# Controller.net
KiCad netlist of a schematic drawn in Altium Designer
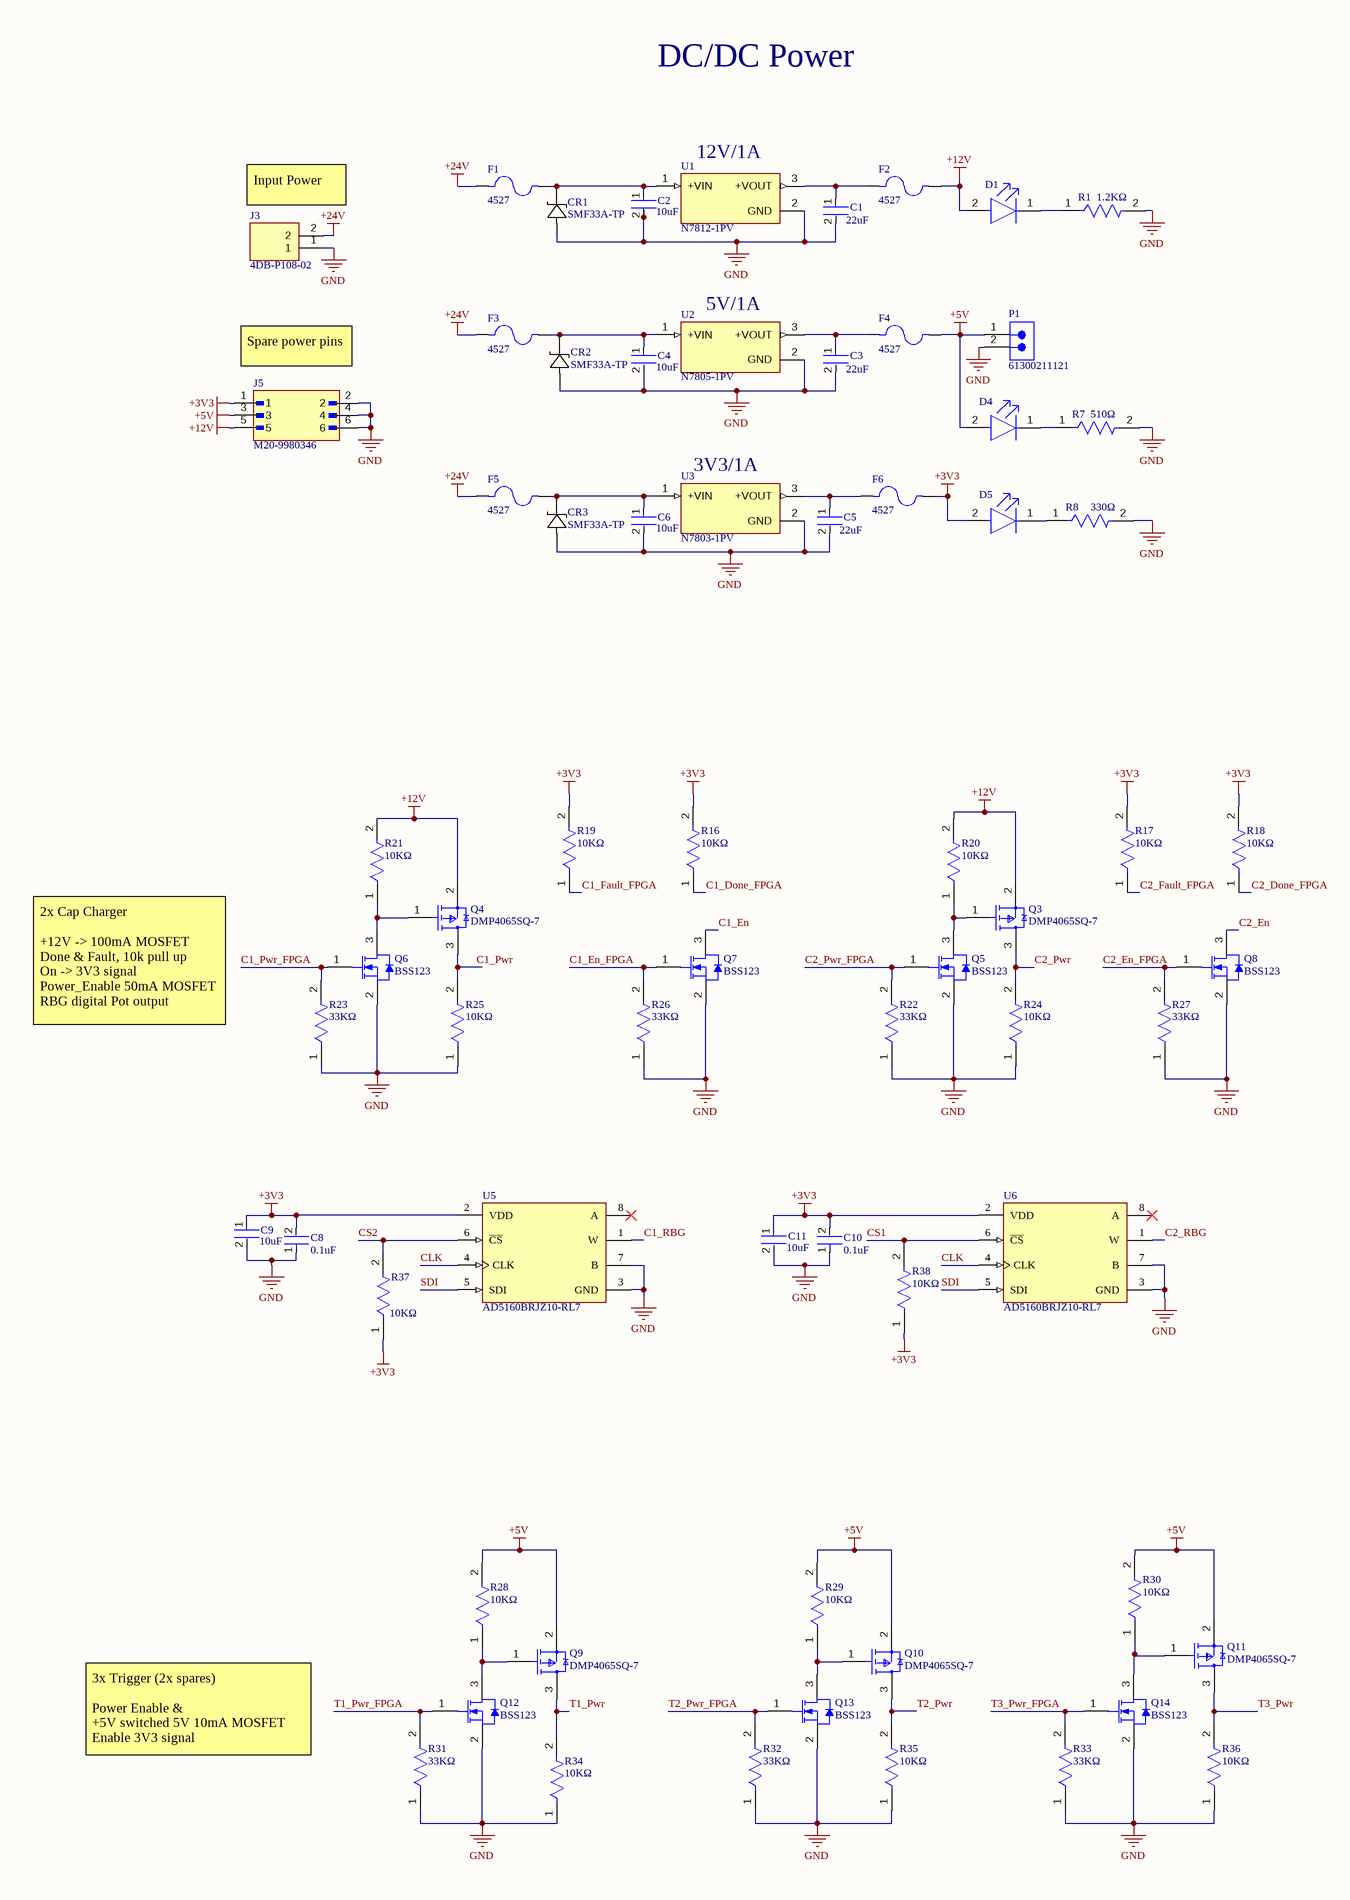
[diagram p0: Controller.SchDoc, left]
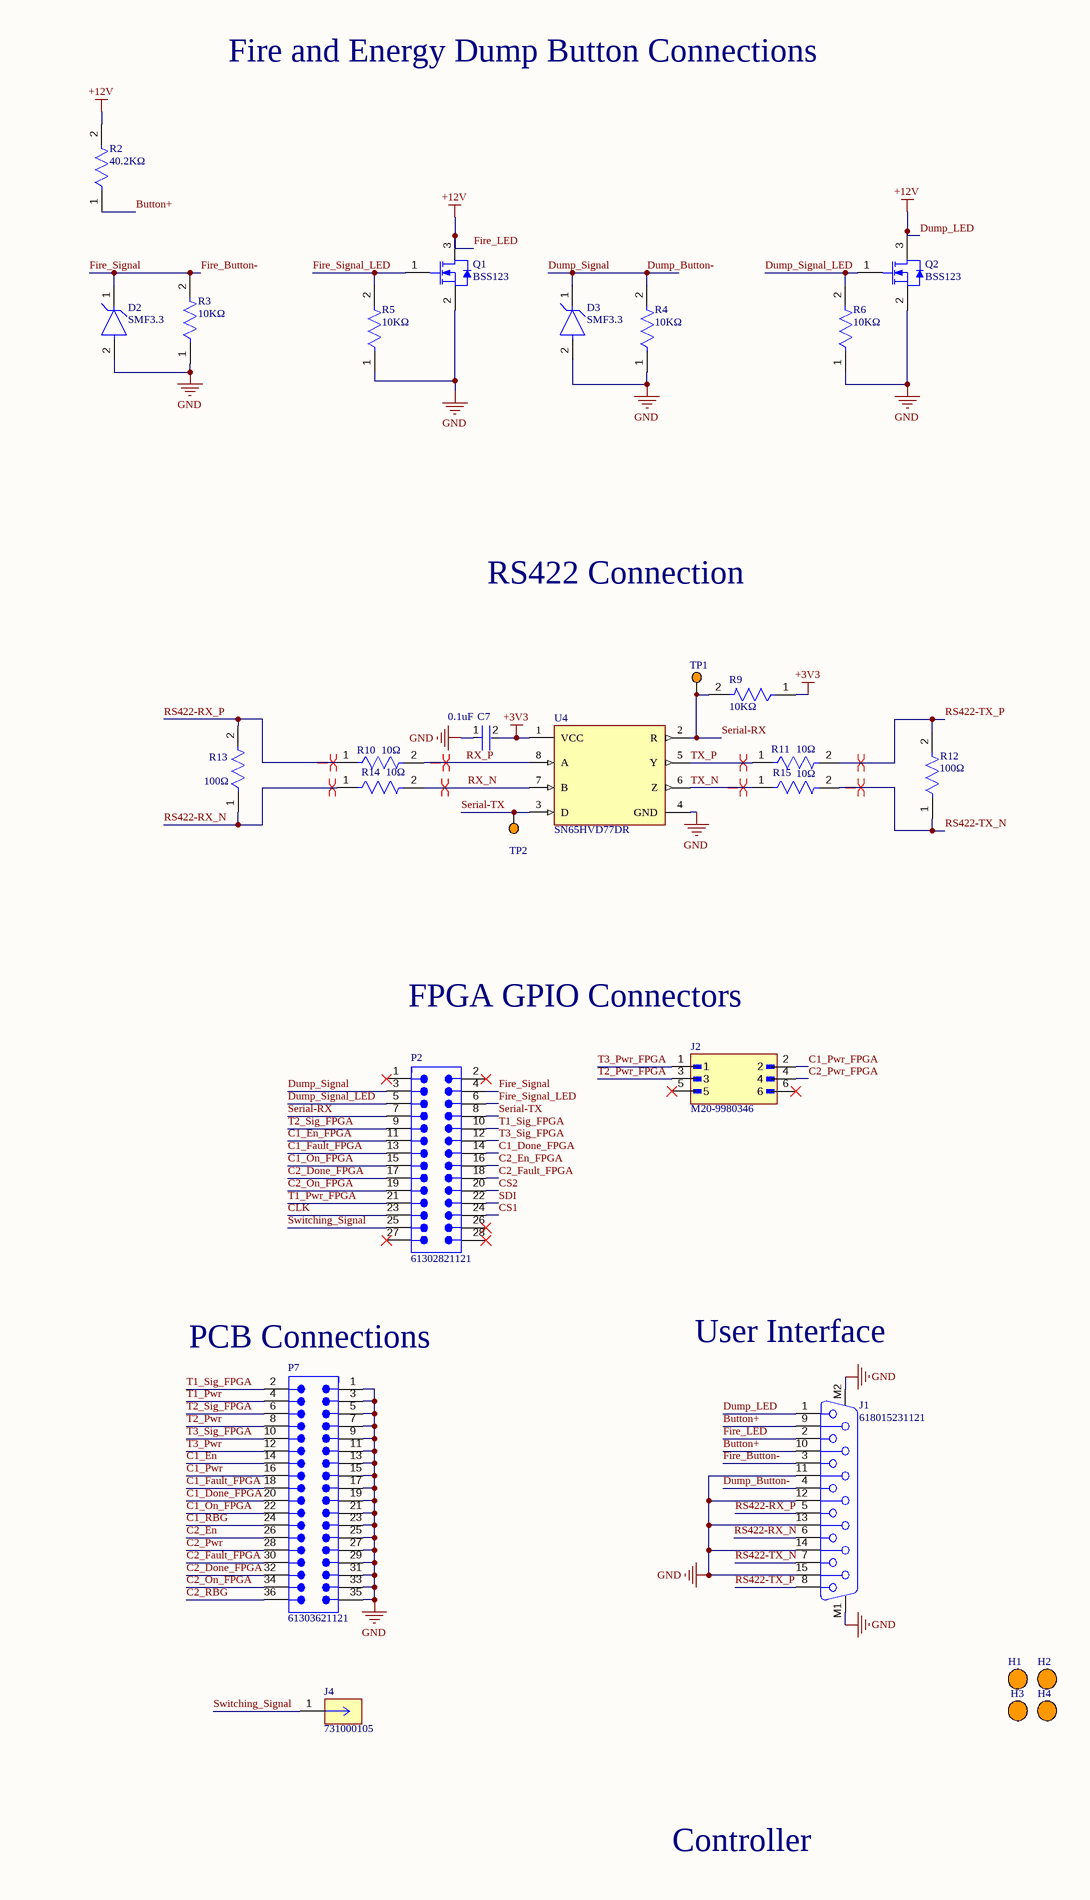
[diagram p1: Controller.SchDoc, right]

(export (version "E")
  (design (tool "Eeschema 10.0.6"))
  (components
    (comp (ref "C1")
      (value "CC0805MKX5R8BB226")
      (footprint "FP-CC0805-0_2-1_45-IPC_C")
      (description "CAP CER 22UF 25V X5R 0805")
      (fields (field (name "CAPACITANCE") "22uF") (field (name "TOLERANCE") "20%"))
      (libsource (lib "Altium Content Vault") (part "11868f565c42a9108669ba33697ecf6"))
    )
    (comp (ref "C2")
      (value "CL32B106KBJNNNE")
      (footprint "FP-CL32-IPC_C")
      (description "Cap Ceramic 10uF 50V X7R ±10% SMD 1210 +125°C Embossed T/R")
      (fields
        (field (name "CAPACITANCE") "10uF")
        (field (name "TOLERANCE") "10%")
        (field (name "VOLTAGE") "50V")
      )
      (libsource (lib "Altium Content Vault") (part "b4654b650e69147ec39a6b967a45e02"))
    )
    (comp (ref "C3")
      (value "CC0805MKX5R8BB226")
      (footprint "FP-CC0805-0_2-1_45-IPC_C")
      (description "CAP CER 22UF 25V X5R 0805")
      (fields (field (name "CAPACITANCE") "22uF") (field (name "TOLERANCE") "20%"))
      (libsource (lib "Altium Content Vault") (part "11868f565c42a9108669ba33697ecf6"))
    )
    (comp (ref "C4")
      (value "CL32B106KBJNNNE")
      (footprint "FP-CL32-IPC_C")
      (description "Cap Ceramic 10uF 50V X7R ±10% SMD 1210 +125°C Embossed T/R")
      (fields
        (field (name "CAPACITANCE") "10uF")
        (field (name "TOLERANCE") "10%")
        (field (name "VOLTAGE") "50V")
      )
      (libsource (lib "Altium Content Vault") (part "b4654b650e69147ec39a6b967a45e02"))
    )
    (comp (ref "C5")
      (value "CC0805MKX5R8BB226")
      (footprint "FP-CC0805-0_2-1_45-IPC_C")
      (description "CAP CER 22UF 25V X5R 0805")
      (fields (field (name "CAPACITANCE") "22uF") (field (name "TOLERANCE") "20%"))
      (libsource (lib "Altium Content Vault") (part "11868f565c42a9108669ba33697ecf6"))
    )
    (comp (ref "C6")
      (value "CL32B106KBJNNNE")
      (footprint "FP-CL32-IPC_C")
      (description "Cap Ceramic 10uF 50V X7R ±10% SMD 1210 +125°C Embossed T/R")
      (fields
        (field (name "CAPACITANCE") "10uF")
        (field (name "TOLERANCE") "10%")
        (field (name "VOLTAGE") "50V")
      )
      (libsource (lib "Altium Content Vault") (part "b4654b650e69147ec39a6b967a45e02"))
    )
    (comp (ref "C7")
      (value "0.1uF")
      (footprint "FP-CC0603-DA-IPC_A")
      (description "CC0603JRX7R9BB104\r\nCAP CER 0.1UF 50V X7R 0603")
      (fields (field (name "TOLERANCE") "5%") (field (name "MANUFACTURER") "Yageo"))
      (libsource (lib "Altium Content Vault") (part "02cd4be3c70576c341d710602a673aa"))
    )
    (comp (ref "C8")
      (value "0.1uF")
      (footprint "FP-CC0603-DA-IPC_A")
      (description "CC0603JRX7R9BB104\r\nCAP CER 0.1UF 50V X7R 0603")
      (fields (field (name "TOLERANCE") "5%") (field (name "MANUFACTURER") "Yageo"))
      (libsource (lib "Altium Content Vault") (part "02cd4be3c70576c341d710602a673aa"))
    )
    (comp (ref "C9")
      (value "CL32B106KBJNNNE")
      (footprint "FP-CL32-IPC_C")
      (description "Cap Ceramic 10uF 50V X7R ±10% SMD 1210 +125°C Embossed T/R")
      (fields
        (field (name "CAPACITANCE") "10uF")
        (field (name "TOLERANCE") "10%")
        (field (name "VOLTAGE") "50V")
      )
      (libsource (lib "Altium Content Vault") (part "b4654b650e69147ec39a6b967a45e02"))
    )
    (comp (ref "C10")
      (value "0.1uF")
      (footprint "FP-CC0603-DA-IPC_A")
      (description "CC0603JRX7R9BB104\r\nCAP CER 0.1UF 50V X7R 0603")
      (fields (field (name "TOLERANCE") "5%") (field (name "MANUFACTURER") "Yageo"))
      (libsource (lib "Altium Content Vault") (part "02cd4be3c70576c341d710602a673aa"))
    )
    (comp (ref "C11")
      (value "CL32B106KBJNNNE")
      (footprint "FP-CL32-IPC_C")
      (description "Cap Ceramic 10uF 50V X7R ±10% SMD 1210 +125°C Embossed T/R")
      (fields
        (field (name "CAPACITANCE") "10uF")
        (field (name "TOLERANCE") "10%")
        (field (name "VOLTAGE") "50V")
      )
      (libsource (lib "Altium Content Vault") (part "b4654b650e69147ec39a6b967a45e02"))
    )
    (comp (ref "CR1")
      (value "SMF33A-TP")
      (footprint "SOD-123FL_MCC")
      (description "No Description Available")
      (fields (field (name "COPYRIGHT") "Copyright (C) 2025 Ultra Librarian. All rights reserved."))
      (libsource (lib "Schlib1") (part "SMF33A-TP"))
    )
    (comp (ref "CR2")
      (value "SMF33A-TP")
      (footprint "SOD-123FL_MCC")
      (description "No Description Available")
      (fields (field (name "COPYRIGHT") "Copyright (C) 2025 Ultra Librarian. All rights reserved."))
      (libsource (lib "Schlib1") (part "SMF33A-TP"))
    )
    (comp (ref "CR3")
      (value "SMF33A-TP")
      (footprint "SOD-123FL_MCC")
      (description "No Description Available")
      (fields (field (name "COPYRIGHT") "Copyright (C) 2025 Ultra Librarian. All rights reserved."))
      (libsource (lib "Schlib1") (part "SMF33A-TP"))
    )
    (comp (ref "D1")
      (value "LTST-C190GKT")
      (footprint "FP-LTST-C190GKT-MFG")
      (description "LED GREEN CLEAR CHIP SMD")
      (fields (field (name "VOLTAGE") "2V"))
      (libsource (lib "Altium Content Vault") (part "8706943c75ba83719d021d2fdc84c58"))
    )
    (comp (ref "D2")
      (value "SMF3.3")
      (footprint "FP-SMF3_3-MFG")
      (description "TVS DIODE 3.3V 6.8V SOD123FL")
      (fields
        (field (name "MANUFACTURER") "Littelfuse")
        (field (name "OCTOPART") "https://octopart.com/smf3.3-littelfuse-75449841")
      )
      (libsource (lib "Altium Content Vault") (part "f813f71cba58e380607f5dd3caf9714"))
    )
    (comp (ref "D3")
      (value "SMF3.3")
      (footprint "FP-SMF3_3-MFG")
      (description "TVS DIODE 3.3V 6.8V SOD123FL")
      (fields
        (field (name "MANUFACTURER") "Littelfuse")
        (field (name "OCTOPART") "https://octopart.com/smf3.3-littelfuse-75449841")
      )
      (libsource (lib "Altium Content Vault") (part "f813f71cba58e380607f5dd3caf9714"))
    )
    (comp (ref "D4")
      (value "LTST-C190GKT")
      (footprint "FP-LTST-C190GKT-MFG")
      (description "LED GREEN CLEAR CHIP SMD")
      (fields (field (name "VOLTAGE") "2V"))
      (libsource (lib "Altium Content Vault") (part "8706943c75ba83719d021d2fdc84c58"))
    )
    (comp (ref "D5")
      (value "LTST-C190GKT")
      (footprint "FP-LTST-C190GKT-MFG")
      (description "LED GREEN CLEAR CHIP SMD")
      (fields (field (name "VOLTAGE") "2V"))
      (libsource (lib "Altium Content Vault") (part "8706943c75ba83719d021d2fdc84c58"))
    )
    (comp (ref "F1")
      (value "4527")
      (footprint "FUSE_4527")
      (description "5mm Low Profile Holder")
      (fields (field (name "MF") "Keystone"))
      (libsource (lib "Schlib1") (part "4527"))
    )
    (comp (ref "F2")
      (value "4527")
      (footprint "FUSE_4527")
      (description "5mm Low Profile Holder")
      (fields (field (name "MF") "Keystone"))
      (libsource (lib "Schlib1") (part "4527"))
    )
    (comp (ref "F3")
      (value "4527")
      (footprint "FUSE_4527")
      (description "5mm Low Profile Holder")
      (fields (field (name "MF") "Keystone"))
      (libsource (lib "Schlib1") (part "4527"))
    )
    (comp (ref "F4")
      (value "4527")
      (footprint "FUSE_4527")
      (description "5mm Low Profile Holder")
      (fields (field (name "MF") "Keystone"))
      (libsource (lib "Schlib1") (part "4527"))
    )
    (comp (ref "F5")
      (value "4527")
      (footprint "FUSE_4527")
      (description "5mm Low Profile Holder")
      (fields (field (name "MF") "Keystone"))
      (libsource (lib "Schlib1") (part "4527"))
    )
    (comp (ref "F6")
      (value "4527")
      (footprint "FUSE_4527")
      (description "5mm Low Profile Holder")
      (fields (field (name "MF") "Keystone"))
      (libsource (lib "Schlib1") (part "4527"))
    )
    (comp (ref "H1") (value "M3_Hole") (footprint "M3_Hole") (libsource (lib "Schlib1") (part "M3_Hole")))
    (comp (ref "H2") (value "M3_Hole") (footprint "M3_Hole") (libsource (lib "Schlib1") (part "M3_Hole")))
    (comp (ref "H3") (value "M3_Hole") (footprint "M3_Hole") (libsource (lib "Schlib1") (part "M3_Hole")))
    (comp (ref "H4") (value "M3_Hole") (footprint "M3_Hole") (libsource (lib "Schlib1") (part "M3_Hole")))
    (comp (ref "J1")
      (value "618015231121")
      (footprint "618015231121")
      (libsource (lib "Altium Content Vault") (part "D-Sub_Female_15p"))
    )
    (comp (ref "J2")
      (value "M20-9980346")
      (footprint "HARWIN_M20-9980346")
      (libsource (lib "Schlib1") (part "M20-9980346"))
    )
    (comp (ref "J3")
      (value "4DB-P108-02")
      (footprint "TE_2-1437667-4")
      (description "Conn; Term Strip; Barrier; 2Pole; 8.26mmPitch; SnglRow; 22-12; Series 4DB; 20A; 150V")
      (fields (field (name "MF") "TE Connectivity"))
      (libsource (lib "Schlib1") (part "4DB-P108-02"))
    )
    (comp (ref "J4")
      (value "731000105")
      (footprint "CONN_73100-0105_MOL")
      (description "BNC JACK, RA, RECEPTACLE, 50 OHM ¦ Molex Incorporated 73100-0105")
      (fields (field (name "MF") "Molex") (field (name "MP") "73100-0105"))
      (libsource (lib "Schlib1") (part "731000105"))
    )
    (comp (ref "J5")
      (value "M20-9980346")
      (footprint "HARWIN_M20-9980346")
      (libsource (lib "Schlib1") (part "M20-9980346"))
    )
    (comp (ref "P1")
      (value "61300211121")
      (footprint "61300211121")
      (libsource (lib "Altium Content Vault") (part "Header_Male_1R_02P"))
    )
    (comp (ref "P2")
      (value "61302821121")
      (footprint "61302821121")
      (libsource (lib "Altium Content Vault") (part "Header_Male_2R_28P"))
    )
    (comp (ref "P7")
      (value "61303621121")
      (footprint "61303621121")
      (libsource (lib "Altium Content Vault") (part "Header_Male_2R_36P"))
    )
    (comp (ref "Q1")
      (value "BSS123")
      (footprint "FAIR-SOT23-3_V")
      (fields (field (name "MANUFACTURER") "Fairchild"))
      (libsource (lib "Altium Content Vault") (part "NEMOS-GSD-3"))
    )
    (comp (ref "Q2")
      (value "BSS123")
      (footprint "FAIR-SOT23-3_V")
      (fields (field (name "MANUFACTURER") "Fairchild"))
      (libsource (lib "Altium Content Vault") (part "NEMOS-GSD-3"))
    )
    (comp (ref "Q3")
      (value "DMP4065SQ-7")
      (footprint "FP-SOT23-IPC_C")
      (description "Mosfet, P-Ch, 40V, 2.4A, 150Deg C, 0.72W")
      (fields (field (name "MANUFACTURER") "Diodes Inc"))
      (libsource (lib "Space Machines Company Pty Ltd") (part "90d26376f95f59a583a7107ec0b7fdb"))
    )
    (comp (ref "Q4")
      (value "DMP4065SQ-7")
      (footprint "FP-SOT23-IPC_C")
      (description "Mosfet, P-Ch, 40V, 2.4A, 150Deg C, 0.72W")
      (fields (field (name "MANUFACTURER") "Diodes Inc"))
      (libsource (lib "Space Machines Company Pty Ltd") (part "90d26376f95f59a583a7107ec0b7fdb"))
    )
    (comp (ref "Q5")
      (value "BSS123")
      (footprint "FAIR-SOT23-3_V")
      (description "Transistor MOSFET Negative Channel 100 Volt 0.17A 3-Pin SOT-23")
      (fields (field (name "MANUFACTURER") "On Semi"))
      (libsource (lib "Space Machines Company Pty Ltd") (part "NEMOS-GSD-3"))
    )
    (comp (ref "Q6")
      (value "BSS123")
      (footprint "FAIR-SOT23-3_V")
      (description "Transistor MOSFET Negative Channel 100 Volt 0.17A 3-Pin SOT-23")
      (fields (field (name "MANUFACTURER") "On Semi"))
      (libsource (lib "Space Machines Company Pty Ltd") (part "NEMOS-GSD-3"))
    )
    (comp (ref "Q7")
      (value "BSS123")
      (footprint "FAIR-SOT23-3_V")
      (description "Transistor MOSFET Negative Channel 100 Volt 0.17A 3-Pin SOT-23")
      (fields (field (name "MANUFACTURER") "On Semi"))
      (libsource (lib "Space Machines Company Pty Ltd") (part "NEMOS-GSD-3"))
    )
    (comp (ref "Q8")
      (value "BSS123")
      (footprint "FAIR-SOT23-3_V")
      (description "Transistor MOSFET Negative Channel 100 Volt 0.17A 3-Pin SOT-23")
      (fields (field (name "MANUFACTURER") "On Semi"))
      (libsource (lib "Space Machines Company Pty Ltd") (part "NEMOS-GSD-3"))
    )
    (comp (ref "Q9")
      (value "DMP4065SQ-7")
      (footprint "FP-SOT23-IPC_C")
      (description "Mosfet, P-Ch, 40V, 2.4A, 150Deg C, 0.72W")
      (fields (field (name "MANUFACTURER") "Diodes Inc"))
      (libsource (lib "Space Machines Company Pty Ltd") (part "90d26376f95f59a583a7107ec0b7fdb"))
    )
    (comp (ref "Q10")
      (value "DMP4065SQ-7")
      (footprint "FP-SOT23-IPC_C")
      (description "Mosfet, P-Ch, 40V, 2.4A, 150Deg C, 0.72W")
      (fields (field (name "MANUFACTURER") "Diodes Inc"))
      (libsource (lib "Space Machines Company Pty Ltd") (part "90d26376f95f59a583a7107ec0b7fdb"))
    )
    (comp (ref "Q11")
      (value "DMP4065SQ-7")
      (footprint "FP-SOT23-IPC_C")
      (description "Mosfet, P-Ch, 40V, 2.4A, 150Deg C, 0.72W")
      (fields (field (name "MANUFACTURER") "Diodes Inc"))
      (libsource (lib "Space Machines Company Pty Ltd") (part "90d26376f95f59a583a7107ec0b7fdb"))
    )
    (comp (ref "Q12")
      (value "BSS123")
      (footprint "FAIR-SOT23-3_V")
      (description "Transistor MOSFET Negative Channel 100 Volt 0.17A 3-Pin SOT-23")
      (fields (field (name "MANUFACTURER") "On Semi"))
      (libsource (lib "Space Machines Company Pty Ltd") (part "NEMOS-GSD-3"))
    )
    (comp (ref "Q13")
      (value "BSS123")
      (footprint "FAIR-SOT23-3_V")
      (description "Transistor MOSFET Negative Channel 100 Volt 0.17A 3-Pin SOT-23")
      (fields (field (name "MANUFACTURER") "On Semi"))
      (libsource (lib "Space Machines Company Pty Ltd") (part "NEMOS-GSD-3"))
    )
    (comp (ref "Q14")
      (value "BSS123")
      (footprint "FAIR-SOT23-3_V")
      (description "Transistor MOSFET Negative Channel 100 Volt 0.17A 3-Pin SOT-23")
      (fields (field (name "MANUFACTURER") "On Semi"))
      (libsource (lib "Space Machines Company Pty Ltd") (part "NEMOS-GSD-3"))
    )
    (comp (ref "R1")
      (value "RT0805FRE071K2L")
      (footprint "FP-RT0805-MFG")
      (description "RES SMD 1.2K OHM 1% 1/8W 0805")
      (fields
        (field (name "TOLERANCE") "0.0001")
        (field (name "RESISTANCE") "1.2KΩ")
        (field (name "OCTOPART") "https://octopart.com/rt0805fre071k2l-yageo-40048706")
      )
      (libsource (lib "Altium Content Vault") (part "1029c3af85768c4190bb7ad29bc67b5"))
    )
    (comp (ref "R2")
      (value "RT0805BRE0740K2L")
      (footprint "FP-RT0805-MFG")
      (description "RES SMD 40.2K OHM 0.1% 1/8W 0805")
      (fields
        (field (name "RESISTANCE") "40.2KΩ")
        (field (name "TOLERANCE") "0.0025")
        (field (name "MANUFACTURER") "Yageo")
      )
      (libsource (lib "Altium Content Vault") (part "1029c3af85768c4190bb7ad29bc67b5"))
    )
    (comp (ref "R3")
      (value "10KΩ")
      (footprint "FP-RT0805-MFG")
      (description "RES 10.0K OHM 1/8W 1% SMD 0805")
      (fields
        (field (name "TOLERANCE") "0.0001")
        (field (name "OCTOPART") "https://octopart.com/rt0805fre0710kl-yageo-40301150")
      )
      (libsource (lib "Altium Content Vault") (part "1029c3af85768c4190bb7ad29bc67b5"))
    )
    (comp (ref "R4")
      (value "10KΩ")
      (footprint "FP-RT0805-MFG")
      (description "RES 10.0K OHM 1/8W 1% SMD 0805")
      (fields
        (field (name "TOLERANCE") "0.0001")
        (field (name "OCTOPART") "https://octopart.com/rt0805fre0710kl-yageo-40301150")
      )
      (libsource (lib "Altium Content Vault") (part "1029c3af85768c4190bb7ad29bc67b5"))
    )
    (comp (ref "R5")
      (value "10KΩ")
      (footprint "FP-RT0805-MFG")
      (description "RES 10.0K OHM 1/8W 1% SMD 0805")
      (fields
        (field (name "TOLERANCE") "0.0001")
        (field (name "OCTOPART") "https://octopart.com/rt0805fre0710kl-yageo-40301150")
      )
      (libsource (lib "Altium Content Vault") (part "1029c3af85768c4190bb7ad29bc67b5"))
    )
    (comp (ref "R6")
      (value "10KΩ")
      (footprint "FP-RT0805-MFG")
      (description "RES 10.0K OHM 1/8W 1% SMD 0805")
      (fields
        (field (name "TOLERANCE") "0.0001")
        (field (name "OCTOPART") "https://octopart.com/rt0805fre0710kl-yageo-40301150")
      )
      (libsource (lib "Altium Content Vault") (part "1029c3af85768c4190bb7ad29bc67b5"))
    )
    (comp (ref "R7")
      (value "RT0805FRE07510RL")
      (footprint "FP-RT0805-MFG")
      (description "RES SMD 510 OHM 1% 1/8W 0805")
      (fields
        (field (name "MANUFACTURER") "Yageo")
        (field (name "OCTOPART") "https://octopart.com/rt0805fre07510rl-yageo-1378875")
        (field (name "RESISTANCE") "510Ω")
      )
      (libsource (lib "Altium Content Vault") (part "1029c3af85768c4190bb7ad29bc67b5"))
    )
    (comp (ref "R8")
      (value "RT0805FRE07330RL")
      (footprint "FP-RT0805-MFG")
      (description "Res Thin Film 0805 330K Ohm 1% 1/8W ±50ppm/°C Molded SMD SMD Paper T/R")
      (fields
        (field (name "OCTOPART") "https://octopart.com/rt0805fre07330rl-yageo-39785396")
        (field (name "RESISTANCE") "330Ω")
        (field (name "MANUFACTURER") "Yageo")
      )
      (libsource (lib "Altium Content Vault") (part "1029c3af85768c4190bb7ad29bc67b5"))
    )
    (comp (ref "R9")
      (value "10KΩ")
      (footprint "FP-RT0805-MFG")
      (description "RES 10.0K OHM 1/8W 1% SMD 0805")
      (fields
        (field (name "TOLERANCE") "0.0001")
        (field (name "OCTOPART") "https://octopart.com/rt0805fre0710kl-yageo-40301150")
      )
      (libsource (lib "Altium Content Vault") (part "1029c3af85768c4190bb7ad29bc67b5"))
    )
    (comp (ref "R10")
      (value "10Ω")
      (footprint "FP-RT0805-MFG")
      (description "RES SMD 10 OHM 1% 1/8W 0805")
      (fields (field (name "TOLERANCE") "0.0001") (field (name "MANUFACTURER PART NUMBER") "RT0805FRE0710RL"))
      (libsource (lib "Altium Content Vault") (part "1029c3af85768c4190bb7ad29bc67b5"))
    )
    (comp (ref "R11")
      (value "10Ω")
      (footprint "FP-RT0805-MFG")
      (description "RES SMD 10 OHM 1% 1/8W 0805")
      (fields (field (name "TOLERANCE") "0.0001") (field (name "MANUFACTURER PART NUMBER") "RT0805FRE0710RL"))
      (libsource (lib "Altium Content Vault") (part "1029c3af85768c4190bb7ad29bc67b5"))
    )
    (comp (ref "R12")
      (value "RT0805FRE07100RL")
      (footprint "FP-RT0805-MFG")
      (description "RES SMD 100 OHM 1% 1/8W 0805")
      (fields
        (field (name "OCTOPART") "https://octopart.com/rt0805fre07100rl-yageo-39834046")
        (field (name "RESISTANCE") "100Ω")
        (field (name "TOLERANCE") "0.0001")
      )
      (libsource (lib "Altium Content Vault") (part "1029c3af85768c4190bb7ad29bc67b5"))
    )
    (comp (ref "R13")
      (value "RT0805FRE07100RL")
      (footprint "FP-RT0805-MFG")
      (description "RES SMD 100 OHM 1% 1/8W 0805")
      (fields
        (field (name "OCTOPART") "https://octopart.com/rt0805fre07100rl-yageo-39834046")
        (field (name "RESISTANCE") "100Ω")
        (field (name "TOLERANCE") "0.0001")
      )
      (libsource (lib "Altium Content Vault") (part "1029c3af85768c4190bb7ad29bc67b5"))
    )
    (comp (ref "R14")
      (value "10Ω")
      (footprint "FP-RT0805-MFG")
      (description "RES SMD 10 OHM 1% 1/8W 0805")
      (fields (field (name "TOLERANCE") "0.0001") (field (name "MANUFACTURER PART NUMBER") "RT0805FRE0710RL"))
      (libsource (lib "Altium Content Vault") (part "1029c3af85768c4190bb7ad29bc67b5"))
    )
    (comp (ref "R15")
      (value "10Ω")
      (footprint "FP-RT0805-MFG")
      (description "RES SMD 10 OHM 1% 1/8W 0805")
      (fields (field (name "TOLERANCE") "0.0001") (field (name "MANUFACTURER PART NUMBER") "RT0805FRE0710RL"))
      (libsource (lib "Altium Content Vault") (part "1029c3af85768c4190bb7ad29bc67b5"))
    )
    (comp (ref "R16")
      (value "10KΩ")
      (footprint "FP-RT0805-MFG")
      (description "RES 10.0K OHM 1/8W 1% SMD 0805")
      (fields
        (field (name "TOLERANCE") "0.0001")
        (field (name "OCTOPART") "https://octopart.com/rt0805fre0710kl-yageo-40301150")
      )
      (libsource (lib "Altium Content Vault") (part "1029c3af85768c4190bb7ad29bc67b5"))
    )
    (comp (ref "R17")
      (value "10KΩ")
      (footprint "FP-RT0805-MFG")
      (description "RES 10.0K OHM 1/8W 1% SMD 0805")
      (fields
        (field (name "TOLERANCE") "0.0001")
        (field (name "OCTOPART") "https://octopart.com/rt0805fre0710kl-yageo-40301150")
      )
      (libsource (lib "Altium Content Vault") (part "1029c3af85768c4190bb7ad29bc67b5"))
    )
    (comp (ref "R18")
      (value "10KΩ")
      (footprint "FP-RT0805-MFG")
      (description "RES 10.0K OHM 1/8W 1% SMD 0805")
      (fields
        (field (name "TOLERANCE") "0.0001")
        (field (name "OCTOPART") "https://octopart.com/rt0805fre0710kl-yageo-40301150")
      )
      (libsource (lib "Altium Content Vault") (part "1029c3af85768c4190bb7ad29bc67b5"))
    )
    (comp (ref "R19")
      (value "10KΩ")
      (footprint "FP-RT0805-MFG")
      (description "RES 10.0K OHM 1/8W 1% SMD 0805")
      (fields
        (field (name "TOLERANCE") "0.0001")
        (field (name "OCTOPART") "https://octopart.com/rt0805fre0710kl-yageo-40301150")
      )
      (libsource (lib "Altium Content Vault") (part "1029c3af85768c4190bb7ad29bc67b5"))
    )
    (comp (ref "R20")
      (value "10KΩ")
      (footprint "FP-RT0805-MFG")
      (description "RES 10.0K OHM 1/8W 1% SMD 0805")
      (fields
        (field (name "TOLERANCE") "0.0001")
        (field (name "OCTOPART") "https://octopart.com/rt0805fre0710kl-yageo-40301150")
      )
      (libsource (lib "Altium Content Vault") (part "1029c3af85768c4190bb7ad29bc67b5"))
    )
    (comp (ref "R21")
      (value "10KΩ")
      (footprint "FP-RT0805-MFG")
      (description "RES 10.0K OHM 1/8W 1% SMD 0805")
      (fields
        (field (name "TOLERANCE") "0.0001")
        (field (name "OCTOPART") "https://octopart.com/rt0805fre0710kl-yageo-40301150")
      )
      (libsource (lib "Altium Content Vault") (part "1029c3af85768c4190bb7ad29bc67b5"))
    )
    (comp (ref "R22")
      (value "33KΩ")
      (footprint "FP-RT0805-MFG")
      (description "RES 33.0K OHM 1/8W .1% SMD 0805")
      (fields
        (field (name "TOLERANCE") "0.0025")
        (field (name "OCTOPART") "https://octopart.com/rt0805brd0733kl-yageo-1457874")
      )
      (libsource (lib "Altium Content Vault") (part "1029c3af85768c4190bb7ad29bc67b5"))
    )
    (comp (ref "R23")
      (value "33KΩ")
      (footprint "FP-RT0805-MFG")
      (description "RES 33.0K OHM 1/8W .1% SMD 0805")
      (fields
        (field (name "TOLERANCE") "0.0025")
        (field (name "OCTOPART") "https://octopart.com/rt0805brd0733kl-yageo-1457874")
      )
      (libsource (lib "Altium Content Vault") (part "1029c3af85768c4190bb7ad29bc67b5"))
    )
    (comp (ref "R24")
      (value "10KΩ")
      (footprint "FP-RT0805-MFG")
      (description "RES 10.0K OHM 1/8W 1% SMD 0805")
      (fields
        (field (name "TOLERANCE") "0.0001")
        (field (name "OCTOPART") "https://octopart.com/rt0805fre0710kl-yageo-40301150")
      )
      (libsource (lib "Altium Content Vault") (part "1029c3af85768c4190bb7ad29bc67b5"))
    )
    (comp (ref "R25")
      (value "10KΩ")
      (footprint "FP-RT0805-MFG")
      (description "RES 10.0K OHM 1/8W 1% SMD 0805")
      (fields
        (field (name "TOLERANCE") "0.0001")
        (field (name "OCTOPART") "https://octopart.com/rt0805fre0710kl-yageo-40301150")
      )
      (libsource (lib "Altium Content Vault") (part "1029c3af85768c4190bb7ad29bc67b5"))
    )
    (comp (ref "R26")
      (value "33KΩ")
      (footprint "FP-RT0805-MFG")
      (description "RES 33.0K OHM 1/8W .1% SMD 0805")
      (fields
        (field (name "TOLERANCE") "0.0025")
        (field (name "OCTOPART") "https://octopart.com/rt0805brd0733kl-yageo-1457874")
      )
      (libsource (lib "Altium Content Vault") (part "1029c3af85768c4190bb7ad29bc67b5"))
    )
    (comp (ref "R27")
      (value "33KΩ")
      (footprint "FP-RT0805-MFG")
      (description "RES 33.0K OHM 1/8W .1% SMD 0805")
      (fields
        (field (name "TOLERANCE") "0.0025")
        (field (name "OCTOPART") "https://octopart.com/rt0805brd0733kl-yageo-1457874")
      )
      (libsource (lib "Altium Content Vault") (part "1029c3af85768c4190bb7ad29bc67b5"))
    )
    (comp (ref "R28")
      (value "10KΩ")
      (footprint "FP-RT0805-MFG")
      (description "RES 10.0K OHM 1/8W 1% SMD 0805")
      (fields
        (field (name "TOLERANCE") "0.0001")
        (field (name "OCTOPART") "https://octopart.com/rt0805fre0710kl-yageo-40301150")
      )
      (libsource (lib "Altium Content Vault") (part "1029c3af85768c4190bb7ad29bc67b5"))
    )
    (comp (ref "R29")
      (value "10KΩ")
      (footprint "FP-RT0805-MFG")
      (description "RES 10.0K OHM 1/8W 1% SMD 0805")
      (fields
        (field (name "TOLERANCE") "0.0001")
        (field (name "OCTOPART") "https://octopart.com/rt0805fre0710kl-yageo-40301150")
      )
      (libsource (lib "Altium Content Vault") (part "1029c3af85768c4190bb7ad29bc67b5"))
    )
    (comp (ref "R30")
      (value "10KΩ")
      (footprint "FP-RT0805-MFG")
      (description "RES 10.0K OHM 1/8W 1% SMD 0805")
      (fields
        (field (name "TOLERANCE") "0.0001")
        (field (name "OCTOPART") "https://octopart.com/rt0805fre0710kl-yageo-40301150")
      )
      (libsource (lib "Altium Content Vault") (part "1029c3af85768c4190bb7ad29bc67b5"))
    )
    (comp (ref "R31")
      (value "33KΩ")
      (footprint "FP-RT0805-MFG")
      (description "RES 33.0K OHM 1/8W .1% SMD 0805")
      (fields
        (field (name "TOLERANCE") "0.0025")
        (field (name "OCTOPART") "https://octopart.com/rt0805brd0733kl-yageo-1457874")
      )
      (libsource (lib "Altium Content Vault") (part "1029c3af85768c4190bb7ad29bc67b5"))
    )
    (comp (ref "R32")
      (value "33KΩ")
      (footprint "FP-RT0805-MFG")
      (description "RES 33.0K OHM 1/8W .1% SMD 0805")
      (fields
        (field (name "TOLERANCE") "0.0025")
        (field (name "OCTOPART") "https://octopart.com/rt0805brd0733kl-yageo-1457874")
      )
      (libsource (lib "Altium Content Vault") (part "1029c3af85768c4190bb7ad29bc67b5"))
    )
    (comp (ref "R33")
      (value "33KΩ")
      (footprint "FP-RT0805-MFG")
      (description "RES 33.0K OHM 1/8W .1% SMD 0805")
      (fields
        (field (name "TOLERANCE") "0.0025")
        (field (name "OCTOPART") "https://octopart.com/rt0805brd0733kl-yageo-1457874")
      )
      (libsource (lib "Altium Content Vault") (part "1029c3af85768c4190bb7ad29bc67b5"))
    )
    (comp (ref "R34")
      (value "10KΩ")
      (footprint "FP-RT0805-MFG")
      (description "RES 10.0K OHM 1/8W 1% SMD 0805")
      (fields
        (field (name "TOLERANCE") "0.0001")
        (field (name "OCTOPART") "https://octopart.com/rt0805fre0710kl-yageo-40301150")
      )
      (libsource (lib "Altium Content Vault") (part "1029c3af85768c4190bb7ad29bc67b5"))
    )
    (comp (ref "R35")
      (value "10KΩ")
      (footprint "FP-RT0805-MFG")
      (description "RES 10.0K OHM 1/8W 1% SMD 0805")
      (fields
        (field (name "TOLERANCE") "0.0001")
        (field (name "OCTOPART") "https://octopart.com/rt0805fre0710kl-yageo-40301150")
      )
      (libsource (lib "Altium Content Vault") (part "1029c3af85768c4190bb7ad29bc67b5"))
    )
    (comp (ref "R36")
      (value "10KΩ")
      (footprint "FP-RT0805-MFG")
      (description "RES 10.0K OHM 1/8W 1% SMD 0805")
      (fields
        (field (name "TOLERANCE") "0.0001")
        (field (name "OCTOPART") "https://octopart.com/rt0805fre0710kl-yageo-40301150")
      )
      (libsource (lib "Altium Content Vault") (part "1029c3af85768c4190bb7ad29bc67b5"))
    )
    (comp (ref "R37")
      (value "10KΩ")
      (footprint "FP-RT0805-MFG")
      (description "RES 10.0K OHM 1/8W 1% SMD 0805")
      (fields
        (field (name "TOLERANCE") "0.0001")
        (field (name "OCTOPART") "https://octopart.com/rt0805fre0710kl-yageo-40301150")
      )
      (libsource (lib "Altium Content Vault") (part "1029c3af85768c4190bb7ad29bc67b5"))
    )
    (comp (ref "R38")
      (value "10KΩ")
      (footprint "FP-RT0805-MFG")
      (description "RES 10.0K OHM 1/8W 1% SMD 0805")
      (fields
        (field (name "TOLERANCE") "0.0001")
        (field (name "OCTOPART") "https://octopart.com/rt0805fre0710kl-yageo-40301150")
      )
      (libsource (lib "Altium Content Vault") (part "1029c3af85768c4190bb7ad29bc67b5"))
    )
    (comp (ref "TP1")
      (value "Test Point")
      (footprint "Test_Pad")
      (description "Just a Pad")
      (fields
        (field (name "MANUFACTURER") "Keystone Electronics")
        (field (name "MANUFACTURER PART NUMBER") "5003")
      )
      (libsource (lib "Schlib1") (part "Test Point"))
    )
    (comp (ref "TP2")
      (value "Test Point")
      (footprint "Test_Pad")
      (description "Just a Pad")
      (fields
        (field (name "MANUFACTURER") "Keystone Electronics")
        (field (name "MANUFACTURER PART NUMBER") "5003")
      )
      (libsource (lib "Schlib1") (part "Test Point"))
    )
    (comp (ref "U1")
      (value "N7812-1PV")
      (footprint "CONV_TSR_1-2433")
      (description "DC-DC Regulated Power Supply Module, 2 Output, 12W, Hybrid")
      (fields (field (name "MANUFACTURER") "Mean Well"))
      (libsource (lib "Schlib1") (part "N7812-1PV"))
    )
    (comp (ref "U2")
      (value "N7805-1PV")
      (footprint "CONV_TSR_1-2433")
      (description "Dc-Dc Converter, 5V, 1A Rohs Compliant: Yes")
      (fields (field (name "MANUFACTURER") "Mean Well"))
      (libsource (lib "Schlib1") (part "N7805-1PV"))
    )
    (comp (ref "U3")
      (value "N7803-1PV")
      (footprint "CONV_TSR_1-2433")
      (description "Dc-Dc Converter, 3.3V, 1A Rohs Compliant: Yes")
      (fields (field (name "MANUFACTURER") "Mean Well"))
      (libsource (lib "Schlib1") (part "N7803-1PV"))
    )
    (comp (ref "U4")
      (value "SN65HVD77DR")
      (footprint "FP-D0008A-IPC_C")
      (description "IC TRANSCEIVER FULL 1/1 8SOIC")
      (fields (field (name "MANUFACTURER") "Texas Instruments"))
      (libsource (lib "Altium Content Vault") (part "831a41f65ddc03463ad534bd5dc70ff"))
    )
    (comp (ref "U5")
      (value "AD5160BRJZ10-RL7")
      (footprint "FP-RJ-8-IPC_B")
      (description "IC DGT POT 10KOHM 256TAP SOT23-8")
      (fields (field (name "TOLERANCE") "15%"))
      (libsource (lib "Altium Content Vault") (part "3b375436e07364a1c44378f04b1ac9c"))
    )
    (comp (ref "U6")
      (value "AD5160BRJZ10-RL7")
      (footprint "FP-RJ-8-IPC_B")
      (description "IC DGT POT 10KOHM 256TAP SOT23-8")
      (fields (field (name "TOLERANCE") "15%"))
      (libsource (lib "Altium Content Vault") (part "3b375436e07364a1c44378f04b1ac9c"))
    )
  )
  (nets
    (net (code "1") (name "+3V3") (class "Default")
      (node (ref "C10") (pin "2") (pinfunction "2_2") (pintype "passive"))
      (node (ref "C11") (pin "1") (pinfunction "1_1") (pintype "passive"))
      (node (ref "C7") (pin "2") (pinfunction "2_2") (pintype "passive"))
      (node (ref "C8") (pin "2") (pinfunction "2_2") (pintype "passive"))
      (node (ref "C9") (pin "1") (pinfunction "1_1") (pintype "passive"))
      (node (ref "D5") (pin "2") (pinfunction "A_2") (pintype "passive"))
      (node (ref "F6") (pin "2") (pinfunction "2_2") (pintype "passive"))
      (node (ref "J5") (pin "1") (pinfunction "1_1") (pintype "passive"))
      (node (ref "R16") (pin "2") (pinfunction "2_2") (pintype "passive"))
      (node (ref "R17") (pin "2") (pinfunction "2_2") (pintype "passive"))
      (node (ref "R18") (pin "2") (pinfunction "2_2") (pintype "passive"))
      (node (ref "R19") (pin "2") (pinfunction "2_2") (pintype "passive"))
      (node (ref "R37") (pin "1") (pinfunction "1_1") (pintype "passive"))
      (node (ref "R38") (pin "1") (pinfunction "1_1") (pintype "passive"))
      (node (ref "R9") (pin "1") (pinfunction "1_1") (pintype "passive"))
      (node (ref "U4") (pin "1") (pinfunction "VCC_1") (pintype "power_in"))
      (node (ref "U5") (pin "2") (pinfunction "VDD_2") (pintype "power_in"))
      (node (ref "U6") (pin "2") (pinfunction "VDD_2") (pintype "power_in"))
    )
    (net (code "2") (name "+5V") (class "Default")
      (node (ref "D4") (pin "2") (pinfunction "A_2") (pintype "passive"))
      (node (ref "F4") (pin "2") (pinfunction "2_2") (pintype "passive"))
      (node (ref "J5") (pin "3") (pinfunction "3_3") (pintype "passive"))
      (node (ref "P1") (pin "1") (pinfunction "1_1") (pintype "passive"))
      (node (ref "Q10") (pin "2") (pinfunction "S_2") (pintype "passive"))
      (node (ref "Q11") (pin "2") (pinfunction "S_2") (pintype "passive"))
      (node (ref "Q9") (pin "2") (pinfunction "S_2") (pintype "passive"))
      (node (ref "R28") (pin "2") (pinfunction "2_2") (pintype "passive"))
      (node (ref "R29") (pin "2") (pinfunction "2_2") (pintype "passive"))
      (node (ref "R30") (pin "2") (pinfunction "2_2") (pintype "passive"))
    )
    (net (code "3") (name "+12V") (class "Default")
      (node (ref "D1") (pin "2") (pinfunction "A_2") (pintype "passive"))
      (node (ref "F2") (pin "2") (pinfunction "2_2") (pintype "passive"))
      (node (ref "J1") (pin "1") (pinfunction "1_1") (pintype "passive"))
      (node (ref "J1") (pin "2") (pinfunction "2_2") (pintype "passive"))
      (node (ref "J5") (pin "5") (pinfunction "5_5") (pintype "passive"))
      (node (ref "Q1") (pin "3") (pinfunction "D_3") (pintype "passive"))
      (node (ref "Q2") (pin "3") (pinfunction "D_3") (pintype "passive"))
      (node (ref "Q3") (pin "2") (pinfunction "S_2") (pintype "passive"))
      (node (ref "Q4") (pin "2") (pinfunction "S_2") (pintype "passive"))
      (node (ref "R2") (pin "2") (pinfunction "2_2") (pintype "passive"))
      (node (ref "R20") (pin "2") (pinfunction "2_2") (pintype "passive"))
      (node (ref "R21") (pin "2") (pinfunction "2_2") (pintype "passive"))
    )
    (net (code "4") (name "+24V") (class "Default")
      (node (ref "F1") (pin "1") (pinfunction "1_1") (pintype "passive"))
      (node (ref "F3") (pin "1") (pinfunction "1_1") (pintype "passive"))
      (node (ref "F5") (pin "1") (pinfunction "1_1") (pintype "passive"))
      (node (ref "J3") (pin "2") (pinfunction "2_2") (pintype "passive"))
    )
    (net (code "5") (name "/Button+") (class "Default")
      (node (ref "J1") (pin "10") (pinfunction "10_10") (pintype "passive"))
      (node (ref "J1") (pin "9") (pinfunction "9_9") (pintype "passive"))
      (node (ref "R2") (pin "1") (pinfunction "1_1") (pintype "passive"))
    )
    (net (code "6") (name "/C1_Done_FPGA") (class "Default")
      (node (ref "P2") (pin "14") (pinfunction "14_14") (pintype "passive"))
      (node (ref "P7") (pin "20") (pinfunction "20_20") (pintype "passive"))
      (node (ref "R16") (pin "1") (pinfunction "1_1") (pintype "passive"))
    )
    (net (code "7") (name "/C1_En") (class "Default")
      (node (ref "P7") (pin "14") (pinfunction "14_14") (pintype "passive"))
      (node (ref "Q7") (pin "3") (pinfunction "D_3") (pintype "passive"))
    )
    (net (code "8") (name "/C1_En_FPGA") (class "Default")
      (node (ref "P2") (pin "11") (pinfunction "11_11") (pintype "passive"))
      (node (ref "Q7") (pin "1") (pinfunction "G_1") (pintype "passive"))
      (node (ref "R26") (pin "2") (pinfunction "2_2") (pintype "passive"))
    )
    (net (code "9") (name "/C1_Fault_FPGA") (class "Default")
      (node (ref "P2") (pin "13") (pinfunction "13_13") (pintype "passive"))
      (node (ref "P7") (pin "18") (pinfunction "18_18") (pintype "passive"))
      (node (ref "R19") (pin "1") (pinfunction "1_1") (pintype "passive"))
    )
    (net (code "10") (name "/C1_On_FPGA") (class "Default")
      (node (ref "P2") (pin "15") (pinfunction "15_15") (pintype "passive"))
      (node (ref "P7") (pin "22") (pinfunction "22_22") (pintype "passive"))
    )
    (net (code "11") (name "/C1_Pwr") (class "Default")
      (node (ref "P7") (pin "16") (pinfunction "16_16") (pintype "passive"))
      (node (ref "Q4") (pin "3") (pinfunction "D_3") (pintype "passive"))
      (node (ref "R25") (pin "2") (pinfunction "2_2") (pintype "passive"))
    )
    (net (code "12") (name "/C1_Pwr_FPGA") (class "Default")
      (node (ref "J2") (pin "2") (pinfunction "2_2") (pintype "passive"))
      (node (ref "Q6") (pin "1") (pinfunction "G_1") (pintype "passive"))
      (node (ref "R23") (pin "2") (pinfunction "2_2") (pintype "passive"))
    )
    (net (code "13") (name "/C1_RBG") (class "Default")
      (node (ref "P7") (pin "24") (pinfunction "24_24") (pintype "passive"))
      (node (ref "U5") (pin "1") (pinfunction "W_1") (pintype "passive"))
    )
    (net (code "14") (name "/C2_Done_FPGA") (class "Default")
      (node (ref "P2") (pin "17") (pinfunction "17_17") (pintype "passive"))
      (node (ref "P7") (pin "32") (pinfunction "32_32") (pintype "passive"))
      (node (ref "R18") (pin "1") (pinfunction "1_1") (pintype "passive"))
    )
    (net (code "15") (name "/C2_En") (class "Default")
      (node (ref "P7") (pin "26") (pinfunction "26_26") (pintype "passive"))
      (node (ref "Q8") (pin "3") (pinfunction "D_3") (pintype "passive"))
    )
    (net (code "16") (name "/C2_En_FPGA") (class "Default")
      (node (ref "P2") (pin "16") (pinfunction "16_16") (pintype "passive"))
      (node (ref "Q8") (pin "1") (pinfunction "G_1") (pintype "passive"))
      (node (ref "R27") (pin "2") (pinfunction "2_2") (pintype "passive"))
    )
    (net (code "17") (name "/C2_Fault_FPGA") (class "Default")
      (node (ref "P2") (pin "18") (pinfunction "18_18") (pintype "passive"))
      (node (ref "P7") (pin "30") (pinfunction "30_30") (pintype "passive"))
      (node (ref "R17") (pin "1") (pinfunction "1_1") (pintype "passive"))
    )
    (net (code "18") (name "/C2_On_FPGA") (class "Default")
      (node (ref "P2") (pin "19") (pinfunction "19_19") (pintype "passive"))
      (node (ref "P7") (pin "34") (pinfunction "34_34") (pintype "passive"))
    )
    (net (code "19") (name "/C2_Pwr") (class "Default")
      (node (ref "P7") (pin "28") (pinfunction "28_28") (pintype "passive"))
      (node (ref "Q3") (pin "3") (pinfunction "D_3") (pintype "passive"))
      (node (ref "R24") (pin "2") (pinfunction "2_2") (pintype "passive"))
    )
    (net (code "20") (name "/C2_Pwr_FPGA") (class "Default")
      (node (ref "J2") (pin "4") (pinfunction "4_4") (pintype "passive"))
      (node (ref "Q5") (pin "1") (pinfunction "G_1") (pintype "passive"))
      (node (ref "R22") (pin "2") (pinfunction "2_2") (pintype "passive"))
    )
    (net (code "21") (name "/C2_RBG") (class "Default")
      (node (ref "P7") (pin "36") (pinfunction "36_36") (pintype "passive"))
      (node (ref "U6") (pin "1") (pinfunction "W_1") (pintype "passive"))
    )
    (net (code "22") (name "/CLK") (class "Default")
      (node (ref "P2") (pin "23") (pinfunction "23_23") (pintype "passive"))
      (node (ref "U5") (pin "4") (pinfunction "CLK_4") (pintype "input"))
      (node (ref "U6") (pin "4") (pinfunction "CLK_4") (pintype "input"))
    )
    (net (code "23") (name "/CS1") (class "Default")
      (node (ref "P2") (pin "24") (pinfunction "24_24") (pintype "passive"))
      (node (ref "R38") (pin "2") (pinfunction "2_2") (pintype "passive"))
      (node (ref "U6") (pin "6") (pinfunction "~{CS}_6") (pintype "input"))
    )
    (net (code "24") (name "/CS2") (class "Default")
      (node (ref "P2") (pin "20") (pinfunction "20_20") (pintype "passive"))
      (node (ref "R37") (pin "2") (pinfunction "2_2") (pintype "passive"))
      (node (ref "U5") (pin "6") (pinfunction "~{CS}_6") (pintype "input"))
    )
    (net (code "25") (name "/Dump_Button-") (class "Default")
      (node (ref "D3") (pin "1") (pinfunction "C_1") (pintype "passive"))
      (node (ref "J1") (pin "4") (pinfunction "4_4") (pintype "passive"))
      (node (ref "P2") (pin "3") (pinfunction "3_3") (pintype "passive"))
      (node (ref "R4") (pin "2") (pinfunction "2_2") (pintype "passive"))
    )
    (net (code "26") (name "/Dump_Signal_LED") (class "Default")
      (node (ref "P2") (pin "5") (pinfunction "5_5") (pintype "passive"))
      (node (ref "Q2") (pin "1") (pinfunction "G_1") (pintype "passive"))
      (node (ref "R6") (pin "2") (pinfunction "2_2") (pintype "passive"))
    )
    (net (code "27") (name "/Fire_Button-") (class "Default")
      (node (ref "D2") (pin "1") (pinfunction "C_1") (pintype "passive"))
      (node (ref "J1") (pin "3") (pinfunction "3_3") (pintype "passive"))
      (node (ref "P2") (pin "4") (pinfunction "4_4") (pintype "passive"))
      (node (ref "R3") (pin "2") (pinfunction "2_2") (pintype "passive"))
    )
    (net (code "28") (name "/Fire_Signal_LED") (class "Default")
      (node (ref "P2") (pin "6") (pinfunction "6_6") (pintype "passive"))
      (node (ref "Q1") (pin "1") (pinfunction "G_1") (pintype "passive"))
      (node (ref "R5") (pin "2") (pinfunction "2_2") (pintype "passive"))
    )
    (net (code "29") (name "/RS422-RX_N") (class "Default")
      (node (ref "J1") (pin "6") (pinfunction "6_6") (pintype "passive"))
      (node (ref "R13") (pin "1") (pinfunction "1_1") (pintype "passive"))
      (node (ref "R14") (pin "1") (pinfunction "1_1") (pintype "passive"))
    )
    (net (code "30") (name "/RS422-RX_P") (class "Default")
      (node (ref "J1") (pin "5") (pinfunction "5_5") (pintype "passive"))
      (node (ref "R10") (pin "1") (pinfunction "1_1") (pintype "passive"))
      (node (ref "R13") (pin "2") (pinfunction "2_2") (pintype "passive"))
    )
    (net (code "31") (name "/RS422-TX_N") (class "Default")
      (node (ref "J1") (pin "7") (pinfunction "7_7") (pintype "passive"))
      (node (ref "R12") (pin "1") (pinfunction "1_1") (pintype "passive"))
      (node (ref "R15") (pin "2") (pinfunction "2_2") (pintype "passive"))
    )
    (net (code "32") (name "/RS422-TX_P") (class "Default")
      (node (ref "J1") (pin "8") (pinfunction "8_8") (pintype "passive"))
      (node (ref "R11") (pin "2") (pinfunction "2_2") (pintype "passive"))
      (node (ref "R12") (pin "2") (pinfunction "2_2") (pintype "passive"))
    )
    (net (code "33") (name "/RX_N") (class "Default")
      (node (ref "R14") (pin "2") (pinfunction "2_2") (pintype "passive"))
      (node (ref "U4") (pin "7") (pinfunction "B_7") (pintype "input"))
    )
    (net (code "34") (name "/RX_P") (class "Default")
      (node (ref "R10") (pin "2") (pinfunction "2_2") (pintype "passive"))
      (node (ref "U4") (pin "8") (pinfunction "A_8") (pintype "input"))
    )
    (net (code "35") (name "/SDI") (class "Default")
      (node (ref "P2") (pin "22") (pinfunction "22_22") (pintype "passive"))
      (node (ref "U5") (pin "5") (pinfunction "SDI_5") (pintype "input"))
      (node (ref "U6") (pin "5") (pinfunction "SDI_5") (pintype "input"))
    )
    (net (code "36") (name "/Serial-RX") (class "Default")
      (node (ref "P2") (pin "7") (pinfunction "7_7") (pintype "passive"))
      (node (ref "R9") (pin "2") (pinfunction "2_2") (pintype "passive"))
      (node (ref "TP1") (pin "1") (pinfunction "T_1") (pintype "passive"))
      (node (ref "U4") (pin "2") (pinfunction "R_2") (pintype "output"))
    )
    (net (code "37") (name "/Serial-TX") (class "Default")
      (node (ref "P2") (pin "8") (pinfunction "8_8") (pintype "passive"))
      (node (ref "TP2") (pin "1") (pinfunction "T_1") (pintype "passive"))
      (node (ref "U4") (pin "3") (pinfunction "D_3") (pintype "input"))
    )
    (net (code "38") (name "/Switching_Signal") (class "Default")
      (node (ref "J4") (pin "1") (pinfunction "1_1") (pintype "passive"))
      (node (ref "P2") (pin "25") (pinfunction "25_25") (pintype "passive"))
    )
    (net (code "39") (name "/T1_Pwr") (class "Default")
      (node (ref "P7") (pin "4") (pinfunction "4_4") (pintype "passive"))
      (node (ref "Q9") (pin "3") (pinfunction "D_3") (pintype "passive"))
      (node (ref "R34") (pin "2") (pinfunction "2_2") (pintype "passive"))
    )
    (net (code "40") (name "/T1_Pwr_FPGA") (class "Default")
      (node (ref "P2") (pin "21") (pinfunction "21_21") (pintype "passive"))
      (node (ref "Q12") (pin "1") (pinfunction "G_1") (pintype "passive"))
      (node (ref "R31") (pin "2") (pinfunction "2_2") (pintype "passive"))
    )
    (net (code "41") (name "/T1_Sig_FPGA") (class "Default")
      (node (ref "P2") (pin "10") (pinfunction "10_10") (pintype "passive"))
      (node (ref "P7") (pin "2") (pinfunction "2_2") (pintype "passive"))
    )
    (net (code "42") (name "/T2_Pwr") (class "Default")
      (node (ref "P7") (pin "8") (pinfunction "8_8") (pintype "passive"))
      (node (ref "Q10") (pin "3") (pinfunction "D_3") (pintype "passive"))
      (node (ref "R35") (pin "2") (pinfunction "2_2") (pintype "passive"))
    )
    (net (code "43") (name "/T2_Pwr_FPGA") (class "Default")
      (node (ref "J2") (pin "3") (pinfunction "3_3") (pintype "passive"))
      (node (ref "Q13") (pin "1") (pinfunction "G_1") (pintype "passive"))
      (node (ref "R32") (pin "2") (pinfunction "2_2") (pintype "passive"))
    )
    (net (code "44") (name "/T2_Sig_FPGA") (class "Default")
      (node (ref "P2") (pin "9") (pinfunction "9_9") (pintype "passive"))
      (node (ref "P7") (pin "6") (pinfunction "6_6") (pintype "passive"))
    )
    (net (code "45") (name "/T3_Pwr") (class "Default")
      (node (ref "P7") (pin "12") (pinfunction "12_12") (pintype "passive"))
      (node (ref "Q11") (pin "3") (pinfunction "D_3") (pintype "passive"))
      (node (ref "R36") (pin "2") (pinfunction "2_2") (pintype "passive"))
    )
    (net (code "46") (name "/T3_Pwr_FPGA") (class "Default")
      (node (ref "J2") (pin "1") (pinfunction "1_1") (pintype "passive"))
      (node (ref "Q14") (pin "1") (pinfunction "G_1") (pintype "passive"))
      (node (ref "R33") (pin "2") (pinfunction "2_2") (pintype "passive"))
    )
    (net (code "47") (name "/T3_Sig_FPGA") (class "Default")
      (node (ref "P2") (pin "12") (pinfunction "12_12") (pintype "passive"))
      (node (ref "P7") (pin "10") (pinfunction "10_10") (pintype "passive"))
    )
    (net (code "48") (name "/TX_N") (class "Default")
      (node (ref "R15") (pin "1") (pinfunction "1_1") (pintype "passive"))
      (node (ref "U4") (pin "6") (pinfunction "Z_6") (pintype "output"))
    )
    (net (code "49") (name "/TX_P") (class "Default")
      (node (ref "R11") (pin "1") (pinfunction "1_1") (pintype "passive"))
      (node (ref "U4") (pin "5") (pinfunction "Y_5") (pintype "output"))
    )
    (net (code "50") (name "GND") (class "Default")
      (node (ref "C1") (pin "2") (pinfunction "2_2") (pintype "passive"))
      (node (ref "C10") (pin "1") (pinfunction "1_1") (pintype "passive"))
      (node (ref "C11") (pin "2") (pinfunction "2_2") (pintype "passive"))
      (node (ref "C2") (pin "2") (pinfunction "2_2") (pintype "passive"))
      (node (ref "C3") (pin "2") (pinfunction "2_2") (pintype "passive"))
      (node (ref "C4") (pin "2") (pinfunction "2_2") (pintype "passive"))
      (node (ref "C5") (pin "2") (pinfunction "2_2") (pintype "passive"))
      (node (ref "C6") (pin "2") (pinfunction "2_2") (pintype "passive"))
      (node (ref "C7") (pin "1") (pinfunction "1_1") (pintype "passive"))
      (node (ref "C8") (pin "1") (pinfunction "1_1") (pintype "passive"))
      (node (ref "C9") (pin "2") (pinfunction "2_2") (pintype "passive"))
      (node (ref "CR1") (pin "2") (pinfunction "2_2") (pintype "passive"))
      (node (ref "CR2") (pin "2") (pinfunction "2_2") (pintype "passive"))
      (node (ref "CR3") (pin "2") (pinfunction "2_2") (pintype "passive"))
      (node (ref "D2") (pin "2") (pinfunction "A_2") (pintype "passive"))
      (node (ref "D3") (pin "2") (pinfunction "A_2") (pintype "passive"))
      (node (ref "J1") (pin "11") (pinfunction "11_11") (pintype "passive"))
      (node (ref "J1") (pin "12") (pinfunction "12_12") (pintype "passive"))
      (node (ref "J1") (pin "13") (pinfunction "13_13") (pintype "passive"))
      (node (ref "J1") (pin "14") (pinfunction "14_14") (pintype "passive"))
      (node (ref "J1") (pin "15") (pinfunction "15_15") (pintype "passive"))
      (node (ref "J1") (pin "M1") (pinfunction "M1_M1") (pintype "passive"))
      (node (ref "J1") (pin "M2") (pinfunction "M2_M2") (pintype "passive"))
      (node (ref "J3") (pin "1") (pinfunction "1_1") (pintype "passive"))
      (node (ref "J5") (pin "2") (pinfunction "2_2") (pintype "passive"))
      (node (ref "J5") (pin "4") (pinfunction "4_4") (pintype "passive"))
      (node (ref "J5") (pin "6") (pinfunction "6_6") (pintype "passive"))
      (node (ref "P1") (pin "2") (pinfunction "2_2") (pintype "passive"))
      (node (ref "P7") (pin "1") (pinfunction "1_1") (pintype "passive"))
      (node (ref "P7") (pin "11") (pinfunction "11_11") (pintype "passive"))
      (node (ref "P7") (pin "13") (pinfunction "13_13") (pintype "passive"))
      (node (ref "P7") (pin "15") (pinfunction "15_15") (pintype "passive"))
      (node (ref "P7") (pin "17") (pinfunction "17_17") (pintype "passive"))
      (node (ref "P7") (pin "19") (pinfunction "19_19") (pintype "passive"))
      (node (ref "P7") (pin "21") (pinfunction "21_21") (pintype "passive"))
      (node (ref "P7") (pin "23") (pinfunction "23_23") (pintype "passive"))
      (node (ref "P7") (pin "25") (pinfunction "25_25") (pintype "passive"))
      (node (ref "P7") (pin "27") (pinfunction "27_27") (pintype "passive"))
      (node (ref "P7") (pin "29") (pinfunction "29_29") (pintype "passive"))
      (node (ref "P7") (pin "3") (pinfunction "3_3") (pintype "passive"))
      (node (ref "P7") (pin "31") (pinfunction "31_31") (pintype "passive"))
      (node (ref "P7") (pin "33") (pinfunction "33_33") (pintype "passive"))
      (node (ref "P7") (pin "35") (pinfunction "35_35") (pintype "passive"))
      (node (ref "P7") (pin "5") (pinfunction "5_5") (pintype "passive"))
      (node (ref "P7") (pin "7") (pinfunction "7_7") (pintype "passive"))
      (node (ref "P7") (pin "9") (pinfunction "9_9") (pintype "passive"))
      (node (ref "Q1") (pin "2") (pinfunction "S_2") (pintype "passive"))
      (node (ref "Q12") (pin "2") (pinfunction "S_2") (pintype "passive"))
      (node (ref "Q13") (pin "2") (pinfunction "S_2") (pintype "passive"))
      (node (ref "Q14") (pin "2") (pinfunction "S_2") (pintype "passive"))
      (node (ref "Q2") (pin "2") (pinfunction "S_2") (pintype "passive"))
      (node (ref "Q5") (pin "2") (pinfunction "S_2") (pintype "passive"))
      (node (ref "Q6") (pin "2") (pinfunction "S_2") (pintype "passive"))
      (node (ref "Q7") (pin "2") (pinfunction "S_2") (pintype "passive"))
      (node (ref "Q8") (pin "2") (pinfunction "S_2") (pintype "passive"))
      (node (ref "R1") (pin "2") (pinfunction "2_2") (pintype "passive"))
      (node (ref "R22") (pin "1") (pinfunction "1_1") (pintype "passive"))
      (node (ref "R23") (pin "1") (pinfunction "1_1") (pintype "passive"))
      (node (ref "R24") (pin "1") (pinfunction "1_1") (pintype "passive"))
      (node (ref "R25") (pin "1") (pinfunction "1_1") (pintype "passive"))
      (node (ref "R26") (pin "1") (pinfunction "1_1") (pintype "passive"))
      (node (ref "R27") (pin "1") (pinfunction "1_1") (pintype "passive"))
      (node (ref "R3") (pin "1") (pinfunction "1_1") (pintype "passive"))
      (node (ref "R31") (pin "1") (pinfunction "1_1") (pintype "passive"))
      (node (ref "R32") (pin "1") (pinfunction "1_1") (pintype "passive"))
      (node (ref "R33") (pin "1") (pinfunction "1_1") (pintype "passive"))
      (node (ref "R34") (pin "1") (pinfunction "1_1") (pintype "passive"))
      (node (ref "R35") (pin "1") (pinfunction "1_1") (pintype "passive"))
      (node (ref "R36") (pin "1") (pinfunction "1_1") (pintype "passive"))
      (node (ref "R4") (pin "1") (pinfunction "1_1") (pintype "passive"))
      (node (ref "R5") (pin "1") (pinfunction "1_1") (pintype "passive"))
      (node (ref "R6") (pin "1") (pinfunction "1_1") (pintype "passive"))
      (node (ref "R7") (pin "2") (pinfunction "2_2") (pintype "passive"))
      (node (ref "R8") (pin "2") (pinfunction "2_2") (pintype "passive"))
      (node (ref "U1") (pin "2") (pinfunction "GND_2") (pintype "power_in"))
      (node (ref "U2") (pin "2") (pinfunction "GND_2") (pintype "power_in"))
      (node (ref "U3") (pin "2") (pinfunction "GND_2") (pintype "power_in"))
      (node (ref "U4") (pin "4") (pinfunction "GND_4") (pintype "power_in"))
      (node (ref "U5") (pin "3") (pinfunction "GND_3") (pintype "power_in"))
      (node (ref "U5") (pin "7") (pinfunction "B_7") (pintype "passive"))
      (node (ref "U6") (pin "3") (pinfunction "GND_3") (pintype "power_in"))
      (node (ref "U6") (pin "7") (pinfunction "B_7") (pintype "passive"))
    )
    (net (code "51") (name "Net-(D1-C)") (class "Default")
      (node (ref "D1") (pin "1") (pinfunction "C_1") (pintype "passive"))
      (node (ref "R1") (pin "1") (pinfunction "1_1") (pintype "passive"))
    )
    (net (code "52") (name "Net-(D4-C)") (class "Default")
      (node (ref "D4") (pin "1") (pinfunction "C_1") (pintype "passive"))
      (node (ref "R7") (pin "1") (pinfunction "1_1") (pintype "passive"))
    )
    (net (code "53") (name "Net-(D5-C)") (class "Default")
      (node (ref "D5") (pin "1") (pinfunction "C_1") (pintype "passive"))
      (node (ref "R8") (pin "1") (pinfunction "1_1") (pintype "passive"))
    )
    (net (code "54") (name "Net-(Q3-G)") (class "Default")
      (node (ref "Q3") (pin "1") (pinfunction "G_1") (pintype "passive"))
      (node (ref "Q5") (pin "3") (pinfunction "D_3") (pintype "passive"))
      (node (ref "R20") (pin "1") (pinfunction "1_1") (pintype "passive"))
    )
    (net (code "55") (name "Net-(Q4-G)") (class "Default")
      (node (ref "Q4") (pin "1") (pinfunction "G_1") (pintype "passive"))
      (node (ref "Q6") (pin "3") (pinfunction "D_3") (pintype "passive"))
      (node (ref "R21") (pin "1") (pinfunction "1_1") (pintype "passive"))
    )
    (net (code "56") (name "Net-(Q10-G)") (class "Default")
      (node (ref "Q10") (pin "1") (pinfunction "G_1") (pintype "passive"))
      (node (ref "Q13") (pin "3") (pinfunction "D_3") (pintype "passive"))
      (node (ref "R29") (pin "1") (pinfunction "1_1") (pintype "passive"))
    )
    (net (code "57") (name "Net-(Q11-G)") (class "Default")
      (node (ref "Q11") (pin "1") (pinfunction "G_1") (pintype "passive"))
      (node (ref "Q14") (pin "3") (pinfunction "D_3") (pintype "passive"))
      (node (ref "R30") (pin "1") (pinfunction "1_1") (pintype "passive"))
    )
    (net (code "58") (name "Net-(Q12-D)") (class "Default")
      (node (ref "Q12") (pin "3") (pinfunction "D_3") (pintype "passive"))
      (node (ref "Q9") (pin "1") (pinfunction "G_1") (pintype "passive"))
      (node (ref "R28") (pin "1") (pinfunction "1_1") (pintype "passive"))
    )
    (net (code "59") (name "Net-(U1-+VIN)") (class "Default")
      (node (ref "C2") (pin "1") (pinfunction "1_1") (pintype "passive"))
      (node (ref "CR1") (pin "1") (pinfunction "1_1") (pintype "passive"))
      (node (ref "F1") (pin "2") (pinfunction "2_2") (pintype "passive"))
      (node (ref "U1") (pin "1") (pinfunction "+VIN_1") (pintype "input"))
    )
    (net (code "60") (name "Net-(U1-+VOUT)") (class "Default")
      (node (ref "C1") (pin "1") (pinfunction "1_1") (pintype "passive"))
      (node (ref "F2") (pin "1") (pinfunction "1_1") (pintype "passive"))
      (node (ref "U1") (pin "3") (pinfunction "+VOUT_3") (pintype "output"))
    )
    (net (code "61") (name "Net-(U2-+VIN)") (class "Default")
      (node (ref "C4") (pin "1") (pinfunction "1_1") (pintype "passive"))
      (node (ref "CR2") (pin "1") (pinfunction "1_1") (pintype "passive"))
      (node (ref "F3") (pin "2") (pinfunction "2_2") (pintype "passive"))
      (node (ref "U2") (pin "1") (pinfunction "+VIN_1") (pintype "input"))
    )
    (net (code "62") (name "Net-(U2-+VOUT)") (class "Default")
      (node (ref "C3") (pin "1") (pinfunction "1_1") (pintype "passive"))
      (node (ref "F4") (pin "1") (pinfunction "1_1") (pintype "passive"))
      (node (ref "U2") (pin "3") (pinfunction "+VOUT_3") (pintype "output"))
    )
    (net (code "63") (name "Net-(U3-+VIN)") (class "Default")
      (node (ref "C6") (pin "1") (pinfunction "1_1") (pintype "passive"))
      (node (ref "CR3") (pin "1") (pinfunction "1_1") (pintype "passive"))
      (node (ref "F5") (pin "2") (pinfunction "2_2") (pintype "passive"))
      (node (ref "U3") (pin "1") (pinfunction "+VIN_1") (pintype "input"))
    )
    (net (code "64") (name "Net-(U3-+VOUT)") (class "Default")
      (node (ref "C5") (pin "1") (pinfunction "1_1") (pintype "passive"))
      (node (ref "F6") (pin "1") (pinfunction "1_1") (pintype "passive"))
      (node (ref "U3") (pin "3") (pinfunction "+VOUT_3") (pintype "output"))
    )
    (net (code "65") (name "unconnected-(J2-Pad5)") (class "Default")
      (node (ref "J2") (pin "5") (pinfunction "5_5") (pintype "passive+no_connect"))
    )
    (net (code "66") (name "unconnected-(J2-Pad6)") (class "Default")
      (node (ref "J2") (pin "6") (pinfunction "6_6") (pintype "passive+no_connect"))
    )
    (net (code "67") (name "unconnected-(P2-Pad1)") (class "Default")
      (node (ref "P2") (pin "1") (pinfunction "1_1") (pintype "passive+no_connect"))
    )
    (net (code "68") (name "unconnected-(P2-Pad2)") (class "Default")
      (node (ref "P2") (pin "2") (pinfunction "2_2") (pintype "passive+no_connect"))
    )
    (net (code "69") (name "unconnected-(P2-Pad26)") (class "Default")
      (node (ref "P2") (pin "26") (pinfunction "26_26") (pintype "passive+no_connect"))
    )
    (net (code "70") (name "unconnected-(P2-Pad27)") (class "Default")
      (node (ref "P2") (pin "27") (pinfunction "27_27") (pintype "passive+no_connect"))
    )
    (net (code "71") (name "unconnected-(P2-Pad28)") (class "Default")
      (node (ref "P2") (pin "28") (pinfunction "28_28") (pintype "passive+no_connect"))
    )
    (net (code "72") (name "unconnected-(U5-A-Pad8)") (class "Default")
      (node (ref "U5") (pin "8") (pinfunction "A_8") (pintype "passive+no_connect"))
    )
    (net (code "73") (name "unconnected-(U6-A-Pad8)") (class "Default")
      (node (ref "U6") (pin "8") (pinfunction "A_8") (pintype "passive+no_connect"))
    )
  )
)
